# SmartSwitchBoard.net
KiCad netlist of a schematic drawn in EAGLE
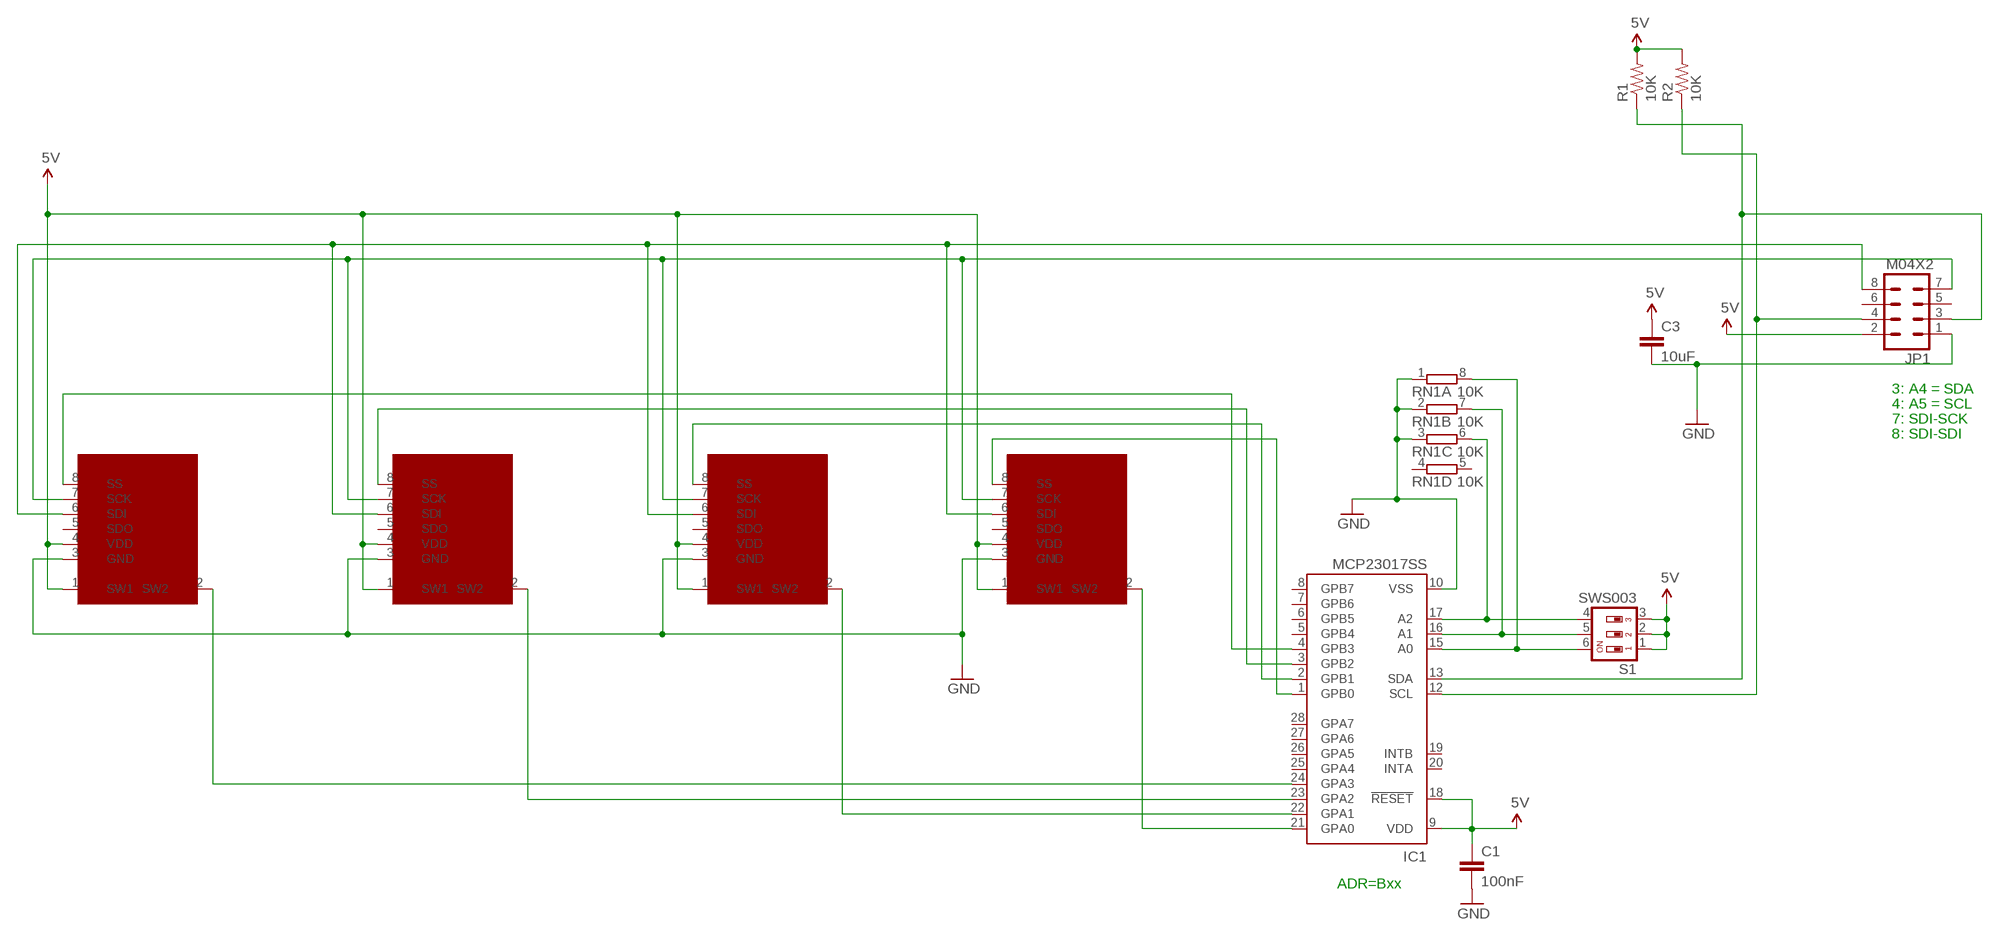
[diagram p0: schematic, sheet 1]

(export (version "E")
  (design (tool "Eeschema 10.0.6"))
  (components
    (comp (ref "C1")
      (value "100nF")
      (footprint "eagle-import:0603-CAP")
      (libsource (lib "eagle-import") (part "CAP0603-CAP"))
    )
    (comp (ref "C3")
      (value "10uF")
      (footprint "eagle-import:0805")
      (libsource (lib "eagle-import") (part "CAP0805"))
    )
    (comp (ref "IC1")
      (value "MCP23017SS")
      (footprint "eagle-import:SSOP28")
      (fields
        (field (name "MF") "MICROCHIP")
        (field (name "MPN") "MCP23017-E/SS")
        (field (name "MPN_1") "MCP23017-E/SS")
        (field (name "OC_FARNELL") "1467674")
        (field (name "OC_NEWARK") "31K2960")
      )
      (libsource (lib "eagle-import") (part "MCP23017SS"))
    )
    (comp (ref "JP1")
      (value "M04X2")
      (footprint "eagle-import:2X4")
      (libsource (lib "eagle-import") (part "M04X2"))
    )
    (comp (ref "R1")
      (value "10K")
      (footprint "eagle-import:0603-RES")
      (libsource (lib "eagle-import") (part "RESISTOR0603-RES"))
    )
    (comp (ref "R2")
      (value "10K")
      (footprint "eagle-import:0603-RES")
      (libsource (lib "eagle-import") (part "RESISTOR0603-RES"))
    )
    (comp (ref "RN1")
      (value "10K")
      (footprint "eagle-import:CAY16_HAND")
      (libsource (lib "eagle-import") (part "4R-NCAY16"))
    )
    (comp (ref "S1")
      (value "SWS003")
      (footprint "eagle-import:SMS-003")
      (libsource (lib "eagle-import") (part "SWS003"))
    )
    (comp (ref "U$3")
      (value "SMART_SWITCH")
      (footprint "eagle-import:SMART_SWITCH")
      (libsource (lib "eagle-import") (part "SMART_SWITCH"))
    )
    (comp (ref "U$4")
      (value "SMART_SWITCH")
      (footprint "eagle-import:SMART_SWITCH")
      (libsource (lib "eagle-import") (part "SMART_SWITCH"))
    )
    (comp (ref "U$5")
      (value "SMART_SWITCH")
      (footprint "eagle-import:SMART_SWITCH")
      (libsource (lib "eagle-import") (part "SMART_SWITCH"))
    )
    (comp (ref "U$6")
      (value "SMART_SWITCH")
      (footprint "eagle-import:SMART_SWITCH")
      (libsource (lib "eagle-import") (part "SMART_SWITCH"))
    )
  )
  (nets
    (net (code "1") (name "5V") (class "Default")
      (node (ref "C1") (pin "1") (pinfunction "1_1") (pintype "passive"))
      (node (ref "C3") (pin "1") (pinfunction "1_1") (pintype "passive"))
      (node (ref "IC1") (pin "18") (pinfunction "~{RESET}_18") (pintype "input"))
      (node (ref "IC1") (pin "9") (pinfunction "VDD_9") (pintype "power_in"))
      (node (ref "JP1") (pin "2") (pinfunction "2_2") (pintype "passive"))
      (node (ref "R1") (pin "2") (pinfunction "2_2") (pintype "passive"))
      (node (ref "R2") (pin "2") (pinfunction "2_2") (pintype "passive"))
      (node (ref "S1") (pin "1") (pinfunction "1_1") (pintype "passive"))
      (node (ref "S1") (pin "2") (pinfunction "2_2") (pintype "passive"))
      (node (ref "S1") (pin "3") (pinfunction "3_3") (pintype "passive"))
      (node (ref "U$3") (pin "1") (pinfunction "SW1_1") (pintype "bidirectional"))
      (node (ref "U$3") (pin "4") (pinfunction "VDD_4") (pintype "bidirectional"))
      (node (ref "U$4") (pin "1") (pinfunction "SW1_1") (pintype "bidirectional"))
      (node (ref "U$4") (pin "4") (pinfunction "VDD_4") (pintype "bidirectional"))
      (node (ref "U$5") (pin "1") (pinfunction "SW1_1") (pintype "bidirectional"))
      (node (ref "U$5") (pin "4") (pinfunction "VDD_4") (pintype "bidirectional"))
      (node (ref "U$6") (pin "1") (pinfunction "SW1_1") (pintype "bidirectional"))
      (node (ref "U$6") (pin "4") (pinfunction "VDD_4") (pintype "bidirectional"))
    )
    (net (code "2") (name "GND") (class "Default")
      (node (ref "C1") (pin "2") (pinfunction "2_2") (pintype "passive"))
      (node (ref "C3") (pin "2") (pinfunction "2_2") (pintype "passive"))
      (node (ref "IC1") (pin "10") (pinfunction "VSS_10") (pintype "power_in"))
      (node (ref "JP1") (pin "1") (pinfunction "1_1") (pintype "passive"))
      (node (ref "RN1") (pin "1") (pinfunction "1_1") (pintype "passive"))
      (node (ref "RN1") (pin "2") (pinfunction "1_2") (pintype "passive"))
      (node (ref "RN1") (pin "3") (pinfunction "1_3") (pintype "passive"))
      (node (ref "U$3") (pin "3") (pinfunction "GND_3") (pintype "bidirectional"))
      (node (ref "U$4") (pin "3") (pinfunction "GND_3") (pintype "bidirectional"))
      (node (ref "U$5") (pin "3") (pinfunction "GND_3") (pintype "bidirectional"))
      (node (ref "U$6") (pin "3") (pinfunction "GND_3") (pintype "bidirectional"))
    )
    (net (code "3") (name "Net-(IC1-A0)") (class "Default")
      (node (ref "IC1") (pin "15") (pinfunction "A0_15") (pintype "input"))
      (node (ref "RN1") (pin "8") (pinfunction "2_8") (pintype "passive"))
      (node (ref "S1") (pin "6") (pinfunction "6_6") (pintype "passive"))
    )
    (net (code "4") (name "Net-(IC1-A1)") (class "Default")
      (node (ref "IC1") (pin "16") (pinfunction "A1_16") (pintype "input"))
      (node (ref "RN1") (pin "7") (pinfunction "2_7") (pintype "passive"))
      (node (ref "S1") (pin "5") (pinfunction "5_5") (pintype "passive"))
    )
    (net (code "5") (name "Net-(IC1-A2)") (class "Default")
      (node (ref "IC1") (pin "17") (pinfunction "A2_17") (pintype "input"))
      (node (ref "RN1") (pin "6") (pinfunction "2_6") (pintype "passive"))
      (node (ref "S1") (pin "4") (pinfunction "4_4") (pintype "passive"))
    )
    (net (code "6") (name "Net-(IC1-GPA0)") (class "Default")
      (node (ref "IC1") (pin "21") (pinfunction "GPA0_21") (pintype "bidirectional"))
      (node (ref "U$3") (pin "2") (pinfunction "SW2_2") (pintype "bidirectional"))
    )
    (net (code "7") (name "Net-(IC1-GPA1)") (class "Default")
      (node (ref "IC1") (pin "22") (pinfunction "GPA1_22") (pintype "bidirectional"))
      (node (ref "U$4") (pin "2") (pinfunction "SW2_2") (pintype "bidirectional"))
    )
    (net (code "8") (name "Net-(IC1-GPA2)") (class "Default")
      (node (ref "IC1") (pin "23") (pinfunction "GPA2_23") (pintype "bidirectional"))
      (node (ref "U$5") (pin "2") (pinfunction "SW2_2") (pintype "bidirectional"))
    )
    (net (code "9") (name "Net-(IC1-GPA3)") (class "Default")
      (node (ref "IC1") (pin "24") (pinfunction "GPA3_24") (pintype "bidirectional"))
      (node (ref "U$6") (pin "2") (pinfunction "SW2_2") (pintype "bidirectional"))
    )
    (net (code "10") (name "Net-(IC1-GPB0)") (class "Default")
      (node (ref "IC1") (pin "1") (pinfunction "GPB0_1") (pintype "bidirectional"))
      (node (ref "U$3") (pin "8") (pinfunction "SS_8") (pintype "bidirectional"))
    )
    (net (code "11") (name "Net-(IC1-GPB1)") (class "Default")
      (node (ref "IC1") (pin "2") (pinfunction "GPB1_2") (pintype "bidirectional"))
      (node (ref "U$4") (pin "8") (pinfunction "SS_8") (pintype "bidirectional"))
    )
    (net (code "12") (name "Net-(IC1-GPB2)") (class "Default")
      (node (ref "IC1") (pin "3") (pinfunction "GPB2_3") (pintype "bidirectional"))
      (node (ref "U$5") (pin "8") (pinfunction "SS_8") (pintype "bidirectional"))
    )
    (net (code "13") (name "Net-(IC1-GPB3)") (class "Default")
      (node (ref "IC1") (pin "4") (pinfunction "GPB3_4") (pintype "bidirectional"))
      (node (ref "U$6") (pin "8") (pinfunction "SS_8") (pintype "bidirectional"))
    )
    (net (code "14") (name "Net-(IC1-SCL)") (class "Default")
      (node (ref "IC1") (pin "12") (pinfunction "SCL_12") (pintype "input"))
      (node (ref "JP1") (pin "4") (pinfunction "4_4") (pintype "passive"))
      (node (ref "R2") (pin "1") (pinfunction "1_1") (pintype "passive"))
    )
    (net (code "15") (name "Net-(IC1-SDA)") (class "Default")
      (node (ref "IC1") (pin "13") (pinfunction "SDA_13") (pintype "bidirectional"))
      (node (ref "JP1") (pin "3") (pinfunction "3_3") (pintype "passive"))
      (node (ref "R1") (pin "1") (pinfunction "1_1") (pintype "passive"))
    )
    (net (code "16") (name "Net-(U$3-SCK)") (class "Default")
      (node (ref "JP1") (pin "7") (pinfunction "7_7") (pintype "passive"))
      (node (ref "U$3") (pin "7") (pinfunction "SCK_7") (pintype "bidirectional"))
      (node (ref "U$4") (pin "7") (pinfunction "SCK_7") (pintype "bidirectional"))
      (node (ref "U$5") (pin "7") (pinfunction "SCK_7") (pintype "bidirectional"))
      (node (ref "U$6") (pin "7") (pinfunction "SCK_7") (pintype "bidirectional"))
    )
    (net (code "17") (name "Net-(U$3-SDI)") (class "Default")
      (node (ref "JP1") (pin "8") (pinfunction "8_8") (pintype "passive"))
      (node (ref "U$3") (pin "6") (pinfunction "SDI_6") (pintype "bidirectional"))
      (node (ref "U$4") (pin "6") (pinfunction "SDI_6") (pintype "bidirectional"))
      (node (ref "U$5") (pin "6") (pinfunction "SDI_6") (pintype "bidirectional"))
      (node (ref "U$6") (pin "6") (pinfunction "SDI_6") (pintype "bidirectional"))
    )
    (net (code "18") (name "unconnected-(IC1-GPA4-Pad25)") (class "Default")
      (node (ref "IC1") (pin "25") (pinfunction "GPA4_25") (pintype "bidirectional"))
    )
    (net (code "19") (name "unconnected-(IC1-GPA5-Pad26)") (class "Default")
      (node (ref "IC1") (pin "26") (pinfunction "GPA5_26") (pintype "bidirectional"))
    )
    (net (code "20") (name "unconnected-(IC1-GPA6-Pad27)") (class "Default")
      (node (ref "IC1") (pin "27") (pinfunction "GPA6_27") (pintype "bidirectional"))
    )
    (net (code "21") (name "unconnected-(IC1-GPA7-Pad28)") (class "Default")
      (node (ref "IC1") (pin "28") (pinfunction "GPA7_28") (pintype "bidirectional"))
    )
    (net (code "22") (name "unconnected-(IC1-GPB4-Pad5)") (class "Default")
      (node (ref "IC1") (pin "5") (pinfunction "GPB4_5") (pintype "bidirectional"))
    )
    (net (code "23") (name "unconnected-(IC1-GPB5-Pad6)") (class "Default")
      (node (ref "IC1") (pin "6") (pinfunction "GPB5_6") (pintype "bidirectional"))
    )
    (net (code "24") (name "unconnected-(IC1-GPB6-Pad7)") (class "Default")
      (node (ref "IC1") (pin "7") (pinfunction "GPB6_7") (pintype "bidirectional"))
    )
    (net (code "25") (name "unconnected-(IC1-GPB7-Pad8)") (class "Default")
      (node (ref "IC1") (pin "8") (pinfunction "GPB7_8") (pintype "bidirectional"))
    )
    (net (code "26") (name "unconnected-(IC1-INTA-Pad20)") (class "Default")
      (node (ref "IC1") (pin "20") (pinfunction "INTA_20") (pintype "output"))
    )
    (net (code "27") (name "unconnected-(IC1-INTB-Pad19)") (class "Default")
      (node (ref "IC1") (pin "19") (pinfunction "INTB_19") (pintype "output"))
    )
    (net (code "28") (name "unconnected-(JP1-Pad5)") (class "Default")
      (node (ref "JP1") (pin "5") (pinfunction "5_5") (pintype "passive"))
    )
    (net (code "29") (name "unconnected-(JP1-Pad6)") (class "Default")
      (node (ref "JP1") (pin "6") (pinfunction "6_6") (pintype "passive"))
    )
    (net (code "30") (name "unconnected-(RN1D-1-Pad4)") (class "Default")
      (node (ref "RN1") (pin "4") (pinfunction "1_4") (pintype "passive"))
    )
    (net (code "31") (name "unconnected-(RN1D-2-Pad5)") (class "Default")
      (node (ref "RN1") (pin "5") (pinfunction "2_5") (pintype "passive"))
    )
    (net (code "32") (name "unconnected-(U$3-SDO-Pad5)") (class "Default")
      (node (ref "U$3") (pin "5") (pinfunction "SDO_5") (pintype "bidirectional"))
    )
    (net (code "33") (name "unconnected-(U$4-SDO-Pad5)") (class "Default")
      (node (ref "U$4") (pin "5") (pinfunction "SDO_5") (pintype "bidirectional"))
    )
    (net (code "34") (name "unconnected-(U$5-SDO-Pad5)") (class "Default")
      (node (ref "U$5") (pin "5") (pinfunction "SDO_5") (pintype "bidirectional"))
    )
    (net (code "35") (name "unconnected-(U$6-SDO-Pad5)") (class "Default")
      (node (ref "U$6") (pin "5") (pinfunction "SDO_5") (pintype "bidirectional"))
    )
  )
)
